# MPU6050.net
KiCad netlist of a schematic drawn in Altium Designer
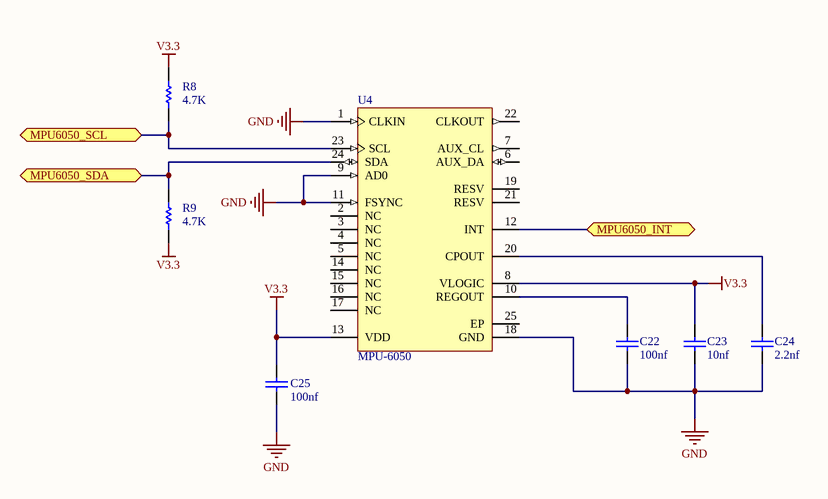
[diagram p0: MPU6050.SchDoc]

(export (version "E")
  (design (tool "Eeschema 10.0.6"))
  (components
    (comp (ref "C22")
      (value "100nf")
      (footprint "CAPC1206(3216)190_N")
      (description "CAP 1206")
      (fields (field (name "TOLERANCE") "Â±10%"))
      (libsource (lib "Altium Content Vault") (part "CAP"))
    )
    (comp (ref "C23")
      (value "10nf")
      (footprint "CAPC1206(3216)190_N")
      (description "CAP 1206")
      (fields (field (name "TOLERANCE") "Â±10%"))
      (libsource (lib "Altium Content Vault") (part "CAP"))
    )
    (comp (ref "C24")
      (value "2.2nf")
      (footprint "CAPC1206(3216)190_N")
      (description "CAP 1206")
      (fields (field (name "TOLERANCE") "Â±10%"))
      (libsource (lib "Altium Content Vault") (part "CAP"))
    )
    (comp (ref "C25")
      (value "100nf")
      (footprint "CAPC1206(3216)190_N")
      (description "CAP 1206")
      (fields (field (name "TOLERANCE") "Â±10%"))
      (libsource (lib "Altium Content Vault") (part "CAP"))
    )
    (comp (ref "R8")
      (value "4.7K")
      (footprint "RESC3216X70X50NL05T20")
      (fields (field (name "MANUFACTURER") "Panasonic") (field (name "PART NUMBER") "ERJ-8GEY0R00V"))
      (libsource (lib "Altium Content Vault") (part "RES"))
    )
    (comp (ref "R9")
      (value "4.7K")
      (footprint "RESC3216X70X50NL05T20")
      (fields (field (name "MANUFACTURER") "Panasonic") (field (name "PART NUMBER") "ERJ-8GEY0R00V"))
      (libsource (lib "Altium Content Vault") (part "RES"))
    )
    (comp (ref "U4")
      (value "MPU-6050")
      (footprint "IS-QFN-24_V")
      (fields (field (name "MANUFACTURER") "InvenSense"))
      (libsource (lib "Altium Content Vault") (part "IS-MPU-6050-QFN-24"))
    )
  )
  (nets
    (net (code "1") (name "/MPU6050_INT") (class "Default")
      (node (ref "U4") (pin "12") (pinfunction "INT_12") (pintype "open_collector"))
    )
    (net (code "2") (name "/MPU6050_SCL") (class "Default")
      (node (ref "R8") (pin "1") (pinfunction "1_1") (pintype "passive"))
      (node (ref "U4") (pin "23") (pinfunction "SCL_23") (pintype "input"))
    )
    (net (code "3") (name "/MPU6050_SDA") (class "Default")
      (node (ref "R9") (pin "2") (pinfunction "2_2") (pintype "passive"))
      (node (ref "U4") (pin "24") (pinfunction "SDA_24") (pintype "bidirectional"))
    )
    (net (code "4") (name "GND") (class "Default")
      (node (ref "C22") (pin "2") (pinfunction "2_2") (pintype "passive"))
      (node (ref "C23") (pin "1") (pinfunction "1_1") (pintype "passive"))
      (node (ref "C24") (pin "1") (pinfunction "1_1") (pintype "passive"))
      (node (ref "C25") (pin "1") (pinfunction "1_1") (pintype "passive"))
      (node (ref "U4") (pin "1") (pinfunction "CLKIN_1") (pintype "input"))
      (node (ref "U4") (pin "11") (pinfunction "FSYNC_11") (pintype "input"))
      (node (ref "U4") (pin "18") (pinfunction "GND_18") (pintype "power_in"))
      (node (ref "U4") (pin "9") (pinfunction "AD0_9") (pintype "input"))
    )
    (net (code "5") (name "Net-(U4-CPOUT)") (class "Default")
      (node (ref "C24") (pin "2") (pinfunction "2_2") (pintype "passive"))
      (node (ref "U4") (pin "20") (pinfunction "CPOUT_20") (pintype "passive"))
    )
    (net (code "6") (name "Net-(U4-REGOUT)") (class "Default")
      (node (ref "C22") (pin "1") (pinfunction "1_1") (pintype "passive"))
      (node (ref "U4") (pin "10") (pinfunction "REGOUT_10") (pintype "passive"))
    )
    (net (code "7") (name "V3.3") (class "Default")
      (node (ref "C23") (pin "2") (pinfunction "2_2") (pintype "passive"))
      (node (ref "C25") (pin "2") (pinfunction "2_2") (pintype "passive"))
      (node (ref "R8") (pin "2") (pinfunction "2_2") (pintype "passive"))
      (node (ref "R9") (pin "1") (pinfunction "1_1") (pintype "passive"))
      (node (ref "U4") (pin "13") (pinfunction "VDD_13") (pintype "power_in"))
      (node (ref "U4") (pin "8") (pinfunction "VLOGIC_8") (pintype "power_in"))
    )
    (net (code "8") (name "unconnected-(U4-AUX_CL-Pad7)") (class "Default")
      (node (ref "U4") (pin "7") (pinfunction "AUX_CL_7") (pintype "output"))
    )
    (net (code "9") (name "unconnected-(U4-AUX_DA-Pad6)") (class "Default")
      (node (ref "U4") (pin "6") (pinfunction "AUX_DA_6") (pintype "bidirectional"))
    )
    (net (code "10") (name "unconnected-(U4-CLKOUT-Pad22)") (class "Default")
      (node (ref "U4") (pin "22") (pinfunction "CLKOUT_22") (pintype "output"))
    )
    (net (code "11") (name "unconnected-(U4-EP-Pad25)") (class "Default")
      (node (ref "U4") (pin "25") (pinfunction "EP_25") (pintype "power_in"))
    )
    (net (code "12") (name "unconnected-(U4-NC-Pad2)") (class "Default")
      (node (ref "U4") (pin "2") (pinfunction "NC_2") (pintype "passive"))
    )
    (net (code "13") (name "unconnected-(U4-NC-Pad3)") (class "Default")
      (node (ref "U4") (pin "3") (pinfunction "NC_3") (pintype "passive"))
    )
    (net (code "14") (name "unconnected-(U4-NC-Pad4)") (class "Default")
      (node (ref "U4") (pin "4") (pinfunction "NC_4") (pintype "passive"))
    )
    (net (code "15") (name "unconnected-(U4-NC-Pad5)") (class "Default")
      (node (ref "U4") (pin "5") (pinfunction "NC_5") (pintype "passive"))
    )
    (net (code "16") (name "unconnected-(U4-NC-Pad14)") (class "Default")
      (node (ref "U4") (pin "14") (pinfunction "NC_14") (pintype "passive"))
    )
    (net (code "17") (name "unconnected-(U4-NC-Pad15)") (class "Default")
      (node (ref "U4") (pin "15") (pinfunction "NC_15") (pintype "passive"))
    )
    (net (code "18") (name "unconnected-(U4-NC-Pad16)") (class "Default")
      (node (ref "U4") (pin "16") (pinfunction "NC_16") (pintype "passive"))
    )
    (net (code "19") (name "unconnected-(U4-NC-Pad17)") (class "Default")
      (node (ref "U4") (pin "17") (pinfunction "NC_17") (pintype "passive"))
    )
    (net (code "20") (name "unconnected-(U4-RESV-Pad19)") (class "Default")
      (node (ref "U4") (pin "19") (pinfunction "RESV_19") (pintype "passive"))
    )
    (net (code "21") (name "unconnected-(U4-RESV-Pad21)") (class "Default")
      (node (ref "U4") (pin "21") (pinfunction "RESV_21") (pintype "passive"))
    )
  )
)
